# uwb_module.net
KiCad netlist of a schematic drawn in Altium Designer
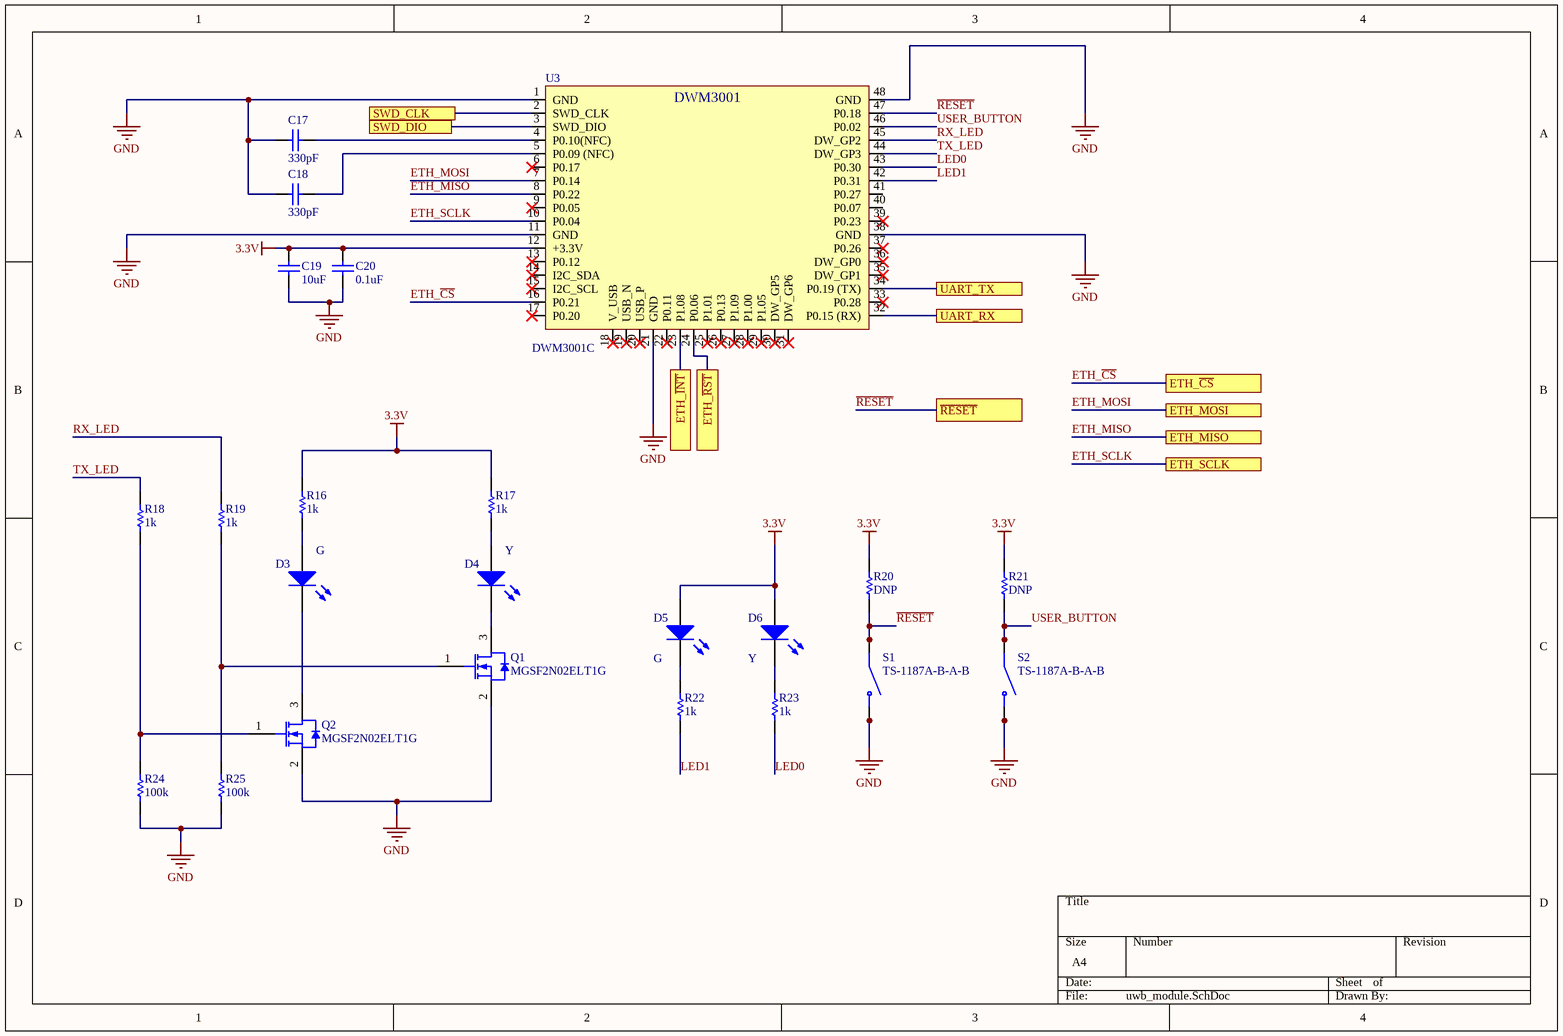
[diagram p0: uwb_module.SchDoc]

(export (version "E")
  (design (tool "Eeschema 10.0.6"))
  (components
    (comp (ref "C17")
      (value "330pF")
      (footprint "0603 - Capacitor")
      (description "Nonpolarized Capacitor")
      (fields
        (field (name "MANUFACTURER") "Samsung Electro-Mechanics")
        (field (name "MANUFACTURER PART NUMBER") "CL10C331JB8NNNC")
      )
      (libsource (lib "General") (part "Capacitor - Nonpolarized"))
    )
    (comp (ref "C18")
      (value "330pF")
      (footprint "0603 - Capacitor")
      (description "Nonpolarized Capacitor")
      (fields
        (field (name "MANUFACTURER") "Samsung Electro-Mechanics")
        (field (name "MANUFACTURER PART NUMBER") "CL10C331JB8NNNC")
      )
      (libsource (lib "General") (part "Capacitor - Nonpolarized"))
    )
    (comp (ref "C19")
      (value "10uF")
      (footprint "0603 - Capacitor")
      (description "Nonpolarized Capacitor")
      (fields
        (field (name "MANUFACTURER") "YAGEO")
        (field (name "MANUFACTURER PART NUMBER") "CC0603KRX7R9BB104")
      )
      (libsource (lib "General") (part "Capacitor - Nonpolarized"))
    )
    (comp (ref "C20")
      (value "0.1uF")
      (footprint "0603 - Capacitor")
      (description "Nonpolarized Capacitor")
      (fields
        (field (name "MANUFACTURER") "YAGEO")
        (field (name "MANUFACTURER PART NUMBER") "CC0603KRX7R9BB104")
      )
      (libsource (lib "General") (part "Capacitor - Nonpolarized"))
    )
    (comp (ref "D3")
      (value "LED")
      (footprint "0805 LED")
      (description "Light Emitting Diode")
      (fields
        (field (name "MANUFACTURER PART NUMBER") "C2297")
        (field (name "MANUFACTURER") "Hubei KENTO Elec")
      )
      (libsource (lib "General") (part "LED"))
    )
    (comp (ref "D4")
      (value "LED")
      (footprint "0805 LED")
      (description "Light Emitting Diode")
      (fields
        (field (name "MANUFACTURER PART NUMBER") "C2296")
        (field (name "MANUFACTURER") "Hubei KENTO Elec")
      )
      (libsource (lib "General") (part "LED"))
    )
    (comp (ref "D5")
      (value "LED")
      (footprint "0805 LED")
      (description "Light Emitting Diode")
      (fields
        (field (name "MANUFACTURER PART NUMBER") "C2297")
        (field (name "MANUFACTURER") "Hubei KENTO Elec")
      )
      (libsource (lib "General") (part "LED"))
    )
    (comp (ref "D6")
      (value "LED")
      (footprint "0805 LED")
      (description "Light Emitting Diode")
      (fields
        (field (name "MANUFACTURER PART NUMBER") "C2296")
        (field (name "MANUFACTURER") "Hubei KENTO Elec")
      )
      (libsource (lib "General") (part "LED"))
    )
    (comp (ref "Q1")
      (value "MGSF2N02ELT1G")
      (footprint "ONSC-SOT-23-3-318-08_V")
      (description "Power MOSFET, 2.8 A, 20 V, N-Channel, 3-Pin SOT-23, Pb-Free, Tape and Reel")
      (fields (field (name "MANUFACTURER") "On Semiconductor"))
      (libsource (lib "Altium Content Vault") (part "ONSC-NMOS-G1S2D3-3"))
    )
    (comp (ref "Q2")
      (value "MGSF2N02ELT1G")
      (footprint "ONSC-SOT-23-3-318-08_V")
      (description "Power MOSFET, 2.8 A, 20 V, N-Channel, 3-Pin SOT-23, Pb-Free, Tape and Reel")
      (fields (field (name "MANUFACTURER") "On Semiconductor"))
      (libsource (lib "Altium Content Vault") (part "ONSC-NMOS-G1S2D3-3"))
    )
    (comp (ref "R16")
      (value "1k")
      (footprint "0603 - Resistor")
      (description "Resistor")
      (fields
        (field (name "MANUFACTURER PART NUMBER") "0603WAF1001T5E")
        (field (name "MANUFACTURER") "UNI-ROYAL(Uniroyal Elec)")
      )
      (libsource (lib "General") (part "Resistor"))
    )
    (comp (ref "R17")
      (value "1k")
      (footprint "0603 - Resistor")
      (description "Resistor")
      (fields
        (field (name "MANUFACTURER PART NUMBER") "0603WAF1001T5E")
        (field (name "MANUFACTURER") "UNI-ROYAL(Uniroyal Elec)")
      )
      (libsource (lib "General") (part "Resistor"))
    )
    (comp (ref "R18")
      (value "1k")
      (footprint "0603 - Resistor")
      (description "Resistor")
      (fields
        (field (name "MANUFACTURER PART NUMBER") "0603WAF1001T5E")
        (field (name "MANUFACTURER") "UNI-ROYAL(Uniroyal Elec)")
      )
      (libsource (lib "General") (part "Resistor"))
    )
    (comp (ref "R19")
      (value "1k")
      (footprint "0603 - Resistor")
      (description "Resistor")
      (fields
        (field (name "MANUFACTURER PART NUMBER") "0603WAF1001T5E")
        (field (name "MANUFACTURER") "UNI-ROYAL(Uniroyal Elec)")
      )
      (libsource (lib "General") (part "Resistor"))
    )
    (comp (ref "R20")
      (value "DNP")
      (footprint "0603 - Resistor")
      (description "Resistor")
      (libsource (lib "General") (part "Resistor"))
    )
    (comp (ref "R21")
      (value "DNP")
      (footprint "0603 - Resistor")
      (description "Resistor")
      (libsource (lib "General") (part "Resistor"))
    )
    (comp (ref "R22")
      (value "1k")
      (footprint "0603 - Resistor")
      (description "Resistor")
      (fields
        (field (name "MANUFACTURER PART NUMBER") "0603WAF1001T5E")
        (field (name "MANUFACTURER") "UNI-ROYAL(Uniroyal Elec)")
      )
      (libsource (lib "General") (part "Resistor"))
    )
    (comp (ref "R23")
      (value "1k")
      (footprint "0603 - Resistor")
      (description "Resistor")
      (fields
        (field (name "MANUFACTURER PART NUMBER") "0603WAF1001T5E")
        (field (name "MANUFACTURER") "UNI-ROYAL(Uniroyal Elec)")
      )
      (libsource (lib "General") (part "Resistor"))
    )
    (comp (ref "R24")
      (value "100k")
      (footprint "0603 - Resistor")
      (description "Resistor")
      (fields
        (field (name "MANUFACTURER PART NUMBER") "0603WAF1003T5E")
        (field (name "MANUFACTURER") "UNI-ROYAL(Uniroyal Elec)")
      )
      (libsource (lib "General") (part "Resistor"))
    )
    (comp (ref "R25")
      (value "100k")
      (footprint "0603 - Resistor")
      (description "Resistor")
      (fields
        (field (name "MANUFACTURER PART NUMBER") "0603WAF1003T5E")
        (field (name "MANUFACTURER") "UNI-ROYAL(Uniroyal Elec)")
      )
      (libsource (lib "General") (part "Resistor"))
    )
    (comp (ref "S1")
      (value "TS-1187A-B-A-B")
      (footprint "SW_TS-1187A-B-A-B")
      (description "SPST 50mA @ 12VDC Top Actuated Round Button 160gf SMD Tactile Switches RoHS")
      (fields (field (name "MANUFACTURER") "XKB Connectivity"))
      (libsource (lib "push_button") (part "TS-1187A-B-A-B"))
    )
    (comp (ref "S2")
      (value "TS-1187A-B-A-B")
      (footprint "SW_TS-1187A-B-A-B")
      (description "SPST 50mA @ 12VDC Top Actuated Round Button 160gf SMD Tactile Switches RoHS")
      (fields (field (name "MANUFACTURER") "XKB Connectivity"))
      (libsource (lib "push_button") (part "TS-1187A-B-A-B"))
    )
    (comp (ref "U3")
      (value "DWM3001C")
      (footprint "DWM3001C")
      (fields (field (name "MANUFACTURER") "Qorvo"))
      (libsource (lib "DWM3001C") (part "DWM3001C"))
    )
  )
  (nets
    (net (code "1") (name "/ETH_MISO") (class "Default")
      (node (ref "U3") (pin "8") (pinfunction "P0.22_8") (pintype "passive"))
    )
    (net (code "2") (name "/ETH_MOSI") (class "Default")
      (node (ref "U3") (pin "7") (pinfunction "P0.14_7") (pintype "passive"))
    )
    (net (code "3") (name "/ETH_SCLK") (class "Default")
      (node (ref "U3") (pin "10") (pinfunction "P0.04_10") (pintype "passive"))
    )
    (net (code "4") (name "/ETH_~{CS}") (class "Default")
      (node (ref "U3") (pin "16") (pinfunction "P0.21_16") (pintype "passive"))
    )
    (net (code "5") (name "/ETH_~{INT}") (class "Default")
      (node (ref "U3") (pin "23") (pinfunction "P1.08_23") (pintype "passive"))
    )
    (net (code "6") (name "/ETH_~{RST}") (class "Default")
      (node (ref "U3") (pin "24") (pinfunction "P0.06_24") (pintype "passive"))
    )
    (net (code "7") (name "/LED0") (class "Default")
      (node (ref "R23") (pin "1") (pinfunction "1_1") (pintype "passive"))
      (node (ref "U3") (pin "43") (pinfunction "P0.30_43") (pintype "passive"))
    )
    (net (code "8") (name "/LED1") (class "Default")
      (node (ref "R22") (pin "1") (pinfunction "1_1") (pintype "passive"))
      (node (ref "U3") (pin "42") (pinfunction "P0.31_42") (pintype "passive"))
    )
    (net (code "9") (name "/RX_LED") (class "Default")
      (node (ref "R19") (pin "2") (pinfunction "2_2") (pintype "passive"))
      (node (ref "U3") (pin "45") (pinfunction "DW_GP2_45") (pintype "passive"))
    )
    (net (code "10") (name "/SWD_CLK") (class "Default")
      (node (ref "U3") (pin "2") (pinfunction "SWD_CLK_2") (pintype "passive"))
    )
    (net (code "11") (name "/SWD_DIO") (class "Default")
      (node (ref "U3") (pin "3") (pinfunction "SWD_DIO_3") (pintype "passive"))
    )
    (net (code "12") (name "/TX_LED") (class "Default")
      (node (ref "R18") (pin "2") (pinfunction "2_2") (pintype "passive"))
      (node (ref "U3") (pin "44") (pinfunction "DW_GP3_44") (pintype "passive"))
    )
    (net (code "13") (name "/UART_RX") (class "Default")
      (node (ref "U3") (pin "32") (pinfunction "P0.15_(RX)_32") (pintype "passive"))
    )
    (net (code "14") (name "/UART_TX") (class "Default")
      (node (ref "U3") (pin "34") (pinfunction "P0.19_(TX)_34") (pintype "passive"))
    )
    (net (code "15") (name "/USER_BUTTON") (class "Default")
      (node (ref "R21") (pin "1") (pinfunction "1_1") (pintype "passive"))
      (node (ref "S2") (pin "A") (pinfunction "COM_A") (pintype "passive"))
      (node (ref "S2") (pin "B") (pinfunction "COM_B") (pintype "passive"))
      (node (ref "U3") (pin "46") (pinfunction "P0.02_46") (pintype "passive"))
    )
    (net (code "16") (name "/~{RESET}") (class "Default")
      (node (ref "R20") (pin "1") (pinfunction "1_1") (pintype "passive"))
      (node (ref "S1") (pin "A") (pinfunction "COM_A") (pintype "passive"))
      (node (ref "S1") (pin "B") (pinfunction "COM_B") (pintype "passive"))
      (node (ref "U3") (pin "47") (pinfunction "P0.18_47") (pintype "passive"))
    )
    (net (code "17") (name "3.3V") (class "Default")
      (node (ref "C19") (pin "1") (pinfunction "1_1") (pintype "passive"))
      (node (ref "C20") (pin "1") (pinfunction "1_1") (pintype "passive"))
      (node (ref "D5") (pin "1") (pinfunction "A_1") (pintype "passive"))
      (node (ref "D6") (pin "1") (pinfunction "A_1") (pintype "passive"))
      (node (ref "R16") (pin "2") (pinfunction "2_2") (pintype "passive"))
      (node (ref "R17") (pin "2") (pinfunction "2_2") (pintype "passive"))
      (node (ref "R20") (pin "2") (pinfunction "2_2") (pintype "passive"))
      (node (ref "R21") (pin "2") (pinfunction "2_2") (pintype "passive"))
      (node (ref "U3") (pin "12") (pinfunction "+3.3V_12") (pintype "passive"))
    )
    (net (code "18") (name "GND") (class "Default")
      (node (ref "C17") (pin "2") (pinfunction "2_2") (pintype "passive"))
      (node (ref "C18") (pin "2") (pinfunction "2_2") (pintype "passive"))
      (node (ref "C19") (pin "2") (pinfunction "2_2") (pintype "passive"))
      (node (ref "C20") (pin "2") (pinfunction "2_2") (pintype "passive"))
      (node (ref "Q1") (pin "2") (pinfunction "S_2") (pintype "passive"))
      (node (ref "Q2") (pin "2") (pinfunction "S_2") (pintype "passive"))
      (node (ref "R24") (pin "1") (pinfunction "1_1") (pintype "passive"))
      (node (ref "R25") (pin "1") (pinfunction "1_1") (pintype "passive"))
      (node (ref "S1") (pin "C") (pinfunction "NO_C") (pintype "passive"))
      (node (ref "S1") (pin "D") (pinfunction "NO_D") (pintype "passive"))
      (node (ref "S2") (pin "C") (pinfunction "NO_C") (pintype "passive"))
      (node (ref "S2") (pin "D") (pinfunction "NO_D") (pintype "passive"))
      (node (ref "U3") (pin "1") (pinfunction "GND_1") (pintype "passive"))
      (node (ref "U3") (pin "11") (pinfunction "GND_11") (pintype "passive"))
      (node (ref "U3") (pin "21") (pinfunction "GND_21") (pintype "passive"))
      (node (ref "U3") (pin "38") (pinfunction "GND_38") (pintype "passive"))
      (node (ref "U3") (pin "48") (pinfunction "GND_48") (pintype "passive"))
    )
    (net (code "19") (name "Net-(D3-A)") (class "Default")
      (node (ref "D3") (pin "1") (pinfunction "A_1") (pintype "passive"))
      (node (ref "R16") (pin "1") (pinfunction "1_1") (pintype "passive"))
    )
    (net (code "20") (name "Net-(D3-K)") (class "Default")
      (node (ref "D3") (pin "2") (pinfunction "K_2") (pintype "passive"))
      (node (ref "Q2") (pin "3") (pinfunction "D_3") (pintype "passive"))
    )
    (net (code "21") (name "Net-(D4-A)") (class "Default")
      (node (ref "D4") (pin "1") (pinfunction "A_1") (pintype "passive"))
      (node (ref "R17") (pin "1") (pinfunction "1_1") (pintype "passive"))
    )
    (net (code "22") (name "Net-(D4-K)") (class "Default")
      (node (ref "D4") (pin "2") (pinfunction "K_2") (pintype "passive"))
      (node (ref "Q1") (pin "3") (pinfunction "D_3") (pintype "passive"))
    )
    (net (code "23") (name "Net-(D5-K)") (class "Default")
      (node (ref "D5") (pin "2") (pinfunction "K_2") (pintype "passive"))
      (node (ref "R22") (pin "2") (pinfunction "2_2") (pintype "passive"))
    )
    (net (code "24") (name "Net-(D6-K)") (class "Default")
      (node (ref "D6") (pin "2") (pinfunction "K_2") (pintype "passive"))
      (node (ref "R23") (pin "2") (pinfunction "2_2") (pintype "passive"))
    )
    (net (code "25") (name "Net-(Q1-G)") (class "Default")
      (node (ref "Q1") (pin "1") (pinfunction "G_1") (pintype "passive"))
      (node (ref "R19") (pin "1") (pinfunction "1_1") (pintype "passive"))
      (node (ref "R25") (pin "2") (pinfunction "2_2") (pintype "passive"))
    )
    (net (code "26") (name "Net-(Q2-G)") (class "Default")
      (node (ref "Q2") (pin "1") (pinfunction "G_1") (pintype "passive"))
      (node (ref "R18") (pin "1") (pinfunction "1_1") (pintype "passive"))
      (node (ref "R24") (pin "2") (pinfunction "2_2") (pintype "passive"))
    )
    (net (code "27") (name "Net-(U3-P0.09_(NFC))") (class "Default")
      (node (ref "C18") (pin "1") (pinfunction "1_1") (pintype "passive"))
      (node (ref "U3") (pin "5") (pinfunction "P0.09_(NFC)_5") (pintype "passive"))
    )
    (net (code "28") (name "Net-(U3-P0.10(NFC))") (class "Default")
      (node (ref "C17") (pin "1") (pinfunction "1_1") (pintype "passive"))
      (node (ref "U3") (pin "4") (pinfunction "P0.10(NFC)_4") (pintype "passive"))
    )
    (net (code "29") (name "unconnected-(U3-DW_GP0-Pad36)") (class "Default")
      (node (ref "U3") (pin "36") (pinfunction "DW_GP0_36") (pintype "passive+no_connect"))
    )
    (net (code "30") (name "unconnected-(U3-DW_GP1-Pad35)") (class "Default")
      (node (ref "U3") (pin "35") (pinfunction "DW_GP1_35") (pintype "passive+no_connect"))
    )
    (net (code "31") (name "unconnected-(U3-DW_GP5-Pad30)") (class "Default")
      (node (ref "U3") (pin "30") (pinfunction "DW_GP5_30") (pintype "passive+no_connect"))
    )
    (net (code "32") (name "unconnected-(U3-DW_GP6-Pad31)") (class "Default")
      (node (ref "U3") (pin "31") (pinfunction "DW_GP6_31") (pintype "passive+no_connect"))
    )
    (net (code "33") (name "unconnected-(U3-I2C_SCL-Pad15)") (class "Default")
      (node (ref "U3") (pin "15") (pinfunction "I2C_SCL_15") (pintype "passive+no_connect"))
    )
    (net (code "34") (name "unconnected-(U3-I2C_SDA-Pad14)") (class "Default")
      (node (ref "U3") (pin "14") (pinfunction "I2C_SDA_14") (pintype "passive+no_connect"))
    )
    (net (code "35") (name "unconnected-(U3-P0.05-Pad9)") (class "Default")
      (node (ref "U3") (pin "9") (pinfunction "P0.05_9") (pintype "passive+no_connect"))
    )
    (net (code "36") (name "unconnected-(U3-P0.07-Pad40)") (class "Default")
      (node (ref "U3") (pin "40") (pinfunction "P0.07_40") (pintype "passive"))
    )
    (net (code "37") (name "unconnected-(U3-P0.11-Pad22)") (class "Default")
      (node (ref "U3") (pin "22") (pinfunction "P0.11_22") (pintype "passive+no_connect"))
    )
    (net (code "38") (name "unconnected-(U3-P0.12-Pad13)") (class "Default")
      (node (ref "U3") (pin "13") (pinfunction "P0.12_13") (pintype "passive+no_connect"))
    )
    (net (code "39") (name "unconnected-(U3-P0.13-Pad26)") (class "Default")
      (node (ref "U3") (pin "26") (pinfunction "P0.13_26") (pintype "passive+no_connect"))
    )
    (net (code "40") (name "unconnected-(U3-P0.17-Pad6)") (class "Default")
      (node (ref "U3") (pin "6") (pinfunction "P0.17_6") (pintype "passive+no_connect"))
    )
    (net (code "41") (name "unconnected-(U3-P0.20-Pad17)") (class "Default")
      (node (ref "U3") (pin "17") (pinfunction "P0.20_17") (pintype "passive+no_connect"))
    )
    (net (code "42") (name "unconnected-(U3-P0.23-Pad39)") (class "Default")
      (node (ref "U3") (pin "39") (pinfunction "P0.23_39") (pintype "passive+no_connect"))
    )
    (net (code "43") (name "unconnected-(U3-P0.26-Pad37)") (class "Default")
      (node (ref "U3") (pin "37") (pinfunction "P0.26_37") (pintype "passive+no_connect"))
    )
    (net (code "44") (name "unconnected-(U3-P0.27-Pad41)") (class "Default")
      (node (ref "U3") (pin "41") (pinfunction "P0.27_41") (pintype "passive"))
    )
    (net (code "45") (name "unconnected-(U3-P0.28-Pad33)") (class "Default")
      (node (ref "U3") (pin "33") (pinfunction "P0.28_33") (pintype "passive+no_connect"))
    )
    (net (code "46") (name "unconnected-(U3-P1.00-Pad28)") (class "Default")
      (node (ref "U3") (pin "28") (pinfunction "P1.00_28") (pintype "passive+no_connect"))
    )
    (net (code "47") (name "unconnected-(U3-P1.01-Pad25)") (class "Default")
      (node (ref "U3") (pin "25") (pinfunction "P1.01_25") (pintype "passive+no_connect"))
    )
    (net (code "48") (name "unconnected-(U3-P1.05-Pad29)") (class "Default")
      (node (ref "U3") (pin "29") (pinfunction "P1.05_29") (pintype "passive+no_connect"))
    )
    (net (code "49") (name "unconnected-(U3-P1.09-Pad27)") (class "Default")
      (node (ref "U3") (pin "27") (pinfunction "P1.09_27") (pintype "passive+no_connect"))
    )
    (net (code "50") (name "unconnected-(U3-USB_N-Pad19)") (class "Default")
      (node (ref "U3") (pin "19") (pinfunction "USB_N_19") (pintype "passive+no_connect"))
    )
    (net (code "51") (name "unconnected-(U3-USB_P-Pad20)") (class "Default")
      (node (ref "U3") (pin "20") (pinfunction "USB_P_20") (pintype "passive+no_connect"))
    )
    (net (code "52") (name "unconnected-(U3-V_USB-Pad18)") (class "Default")
      (node (ref "U3") (pin "18") (pinfunction "V_USB_18") (pintype "passive+no_connect"))
    )
  )
)
